# design.net
KiCad netlist of a schematic drawn in Altium Designer
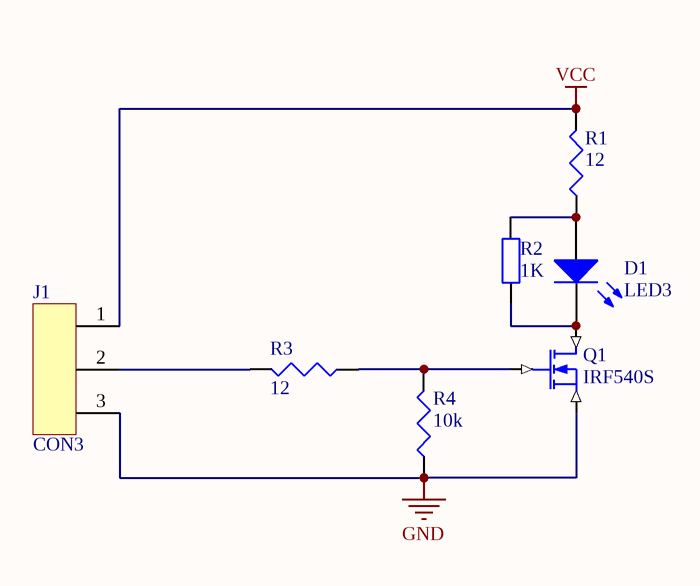
[diagram p0: 原理图.SchDoc]

(export (version "E")
  (design (tool "Eeschema 10.0.6"))
  (components
    (comp (ref "D1")
      (value "LED3")
      (footprint "3.5X2.8X1.9")
      (description "Typical BLUE SiC LED")
      (fields (field (name "PUBLISHER") "Altium Limited"))
      (libsource (lib "Miscellaneous Devices") (part "LED3"))
    )
    (comp (ref "J1")
      (value "CON3")
      (footprint "SIP-3")
      (description "SOCKET")
      (libsource (lib "我的库") (part "CON3"))
    )
    (comp (ref "Q1")
      (value "IRF540S")
      (footprint "TO-263-2")
      (description "N-Channel MOSFET")
      (libsource (lib "我的库") (part "IRF540S"))
    )
    (comp (ref "R1")
      (value "12")
      (footprint "J1-0603")
      (description "Resistor")
      (fields (field (name "PUBLISHER") "Altium Limited"))
      (libsource (lib "Miscellaneous Devices") (part "Res3"))
    )
    (comp (ref "R2")
      (value "1K")
      (footprint "AXIAL0.3")
      (fields (field (name "Comment") "Res"))
      (libsource (lib "科协的库") (part "Res"))
    )
    (comp (ref "R3")
      (value "12")
      (footprint "J1-0603")
      (description "Resistor")
      (fields (field (name "PUBLISHER") "Altium Limited"))
      (libsource (lib "Miscellaneous Devices") (part "Res3"))
    )
    (comp (ref "R4")
      (value "10k")
      (footprint "J1-0603")
      (description "Resistor")
      (fields (field (name "PUBLISHER") "Altium Limited"))
      (libsource (lib "Miscellaneous Devices") (part "Res3"))
    )
  )
  (nets
    (net (code "1") (name "GND") (class "Default")
      (node (ref "J1") (pin "3") (pinfunction "3_3") (pintype "passive"))
      (node (ref "Q1") (pin "3") (pinfunction "S_3") (pintype "input"))
      (node (ref "R4") (pin "1") (pinfunction "1_1") (pintype "passive"))
    )
    (net (code "2") (name "Net-(D1-A)") (class "Default")
      (node (ref "D1") (pin "1") (pinfunction "A_1") (pintype "passive"))
      (node (ref "R1") (pin "1") (pinfunction "1_1") (pintype "passive"))
      (node (ref "R2") (pin "2") (pinfunction "2_2") (pintype "passive"))
    )
    (net (code "3") (name "Net-(D1-K)") (class "Default")
      (node (ref "D1") (pin "2") (pinfunction "K_2") (pintype "passive"))
      (node (ref "Q1") (pin "1") (pinfunction "D_1") (pintype "input"))
      (node (ref "R2") (pin "1") (pinfunction "1_1") (pintype "passive"))
    )
    (net (code "4") (name "Net-(J1-Pad2)") (class "Default")
      (node (ref "J1") (pin "2") (pinfunction "2_2") (pintype "passive"))
      (node (ref "R3") (pin "2") (pinfunction "2_2") (pintype "passive"))
    )
    (net (code "5") (name "Net-(Q1-G)") (class "Default")
      (node (ref "Q1") (pin "2") (pinfunction "G_2") (pintype "input"))
      (node (ref "R3") (pin "1") (pinfunction "1_1") (pintype "passive"))
      (node (ref "R4") (pin "2") (pinfunction "2_2") (pintype "passive"))
    )
    (net (code "6") (name "VCC") (class "Default")
      (node (ref "J1") (pin "1") (pinfunction "1_1") (pintype "passive"))
      (node (ref "R1") (pin "2") (pinfunction "2_2") (pintype "passive"))
    )
  )
)
